# Mech.net
KiCad netlist of a schematic drawn in Altium Designer
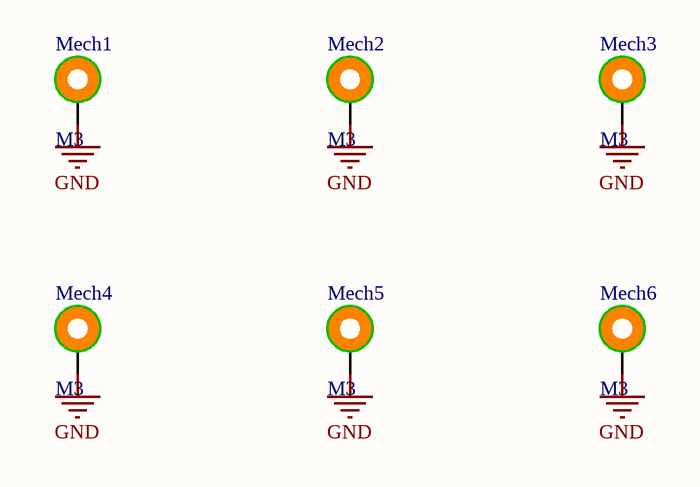
[diagram p0: Mech.SchDoc]

(export (version "E")
  (design (tool "Eeschema 10.0.6"))
  (components
    (comp (ref "Mech1")
      (value "M3")
      (footprint "PCBPad_M3_Head6mm")
      (libsource (lib "PCB Mech__SARAversion-51") (part "PCBPad_M3_Head6mm"))
    )
    (comp (ref "Mech2")
      (value "M3")
      (footprint "PCBPad_M3_Head6mm")
      (libsource (lib "PCB Mech__SARAversion-51") (part "PCBPad_M3_Head6mm"))
    )
    (comp (ref "Mech3")
      (value "M3")
      (footprint "PCBPad_M3_Head6mm")
      (libsource (lib "PCB Mech__SARAversion-51") (part "PCBPad_M3_Head6mm"))
    )
    (comp (ref "Mech4")
      (value "M3")
      (footprint "PCBPad_M3_Head6mm")
      (libsource (lib "PCB Mech__SARAversion-51") (part "PCBPad_M3_Head6mm"))
    )
    (comp (ref "Mech5")
      (value "M3")
      (footprint "PCBPad_M3_Head6mm")
      (libsource (lib "PCB Mech__SARAversion-51") (part "PCBPad_M3_Head6mm"))
    )
    (comp (ref "Mech6")
      (value "M3")
      (footprint "PCBPad_M3_Head6mm")
      (libsource (lib "PCB Mech__SARAversion-51") (part "PCBPad_M3_Head6mm"))
    )
  )
  (nets
    (net (code "1") (name "GND") (class "Default")
      (node (ref "Mech1") (pin "1") (pinfunction "1_1") (pintype "passive"))
      (node (ref "Mech2") (pin "1") (pinfunction "1_1") (pintype "passive"))
      (node (ref "Mech3") (pin "1") (pinfunction "1_1") (pintype "passive"))
      (node (ref "Mech4") (pin "1") (pinfunction "1_1") (pintype "passive"))
      (node (ref "Mech5") (pin "1") (pinfunction "1_1") (pintype "passive"))
      (node (ref "Mech6") (pin "1") (pinfunction "1_1") (pintype "passive"))
    )
  )
)
